# HACKERCARD.net
KiCad netlist of a schematic drawn in EasyEDA Pro
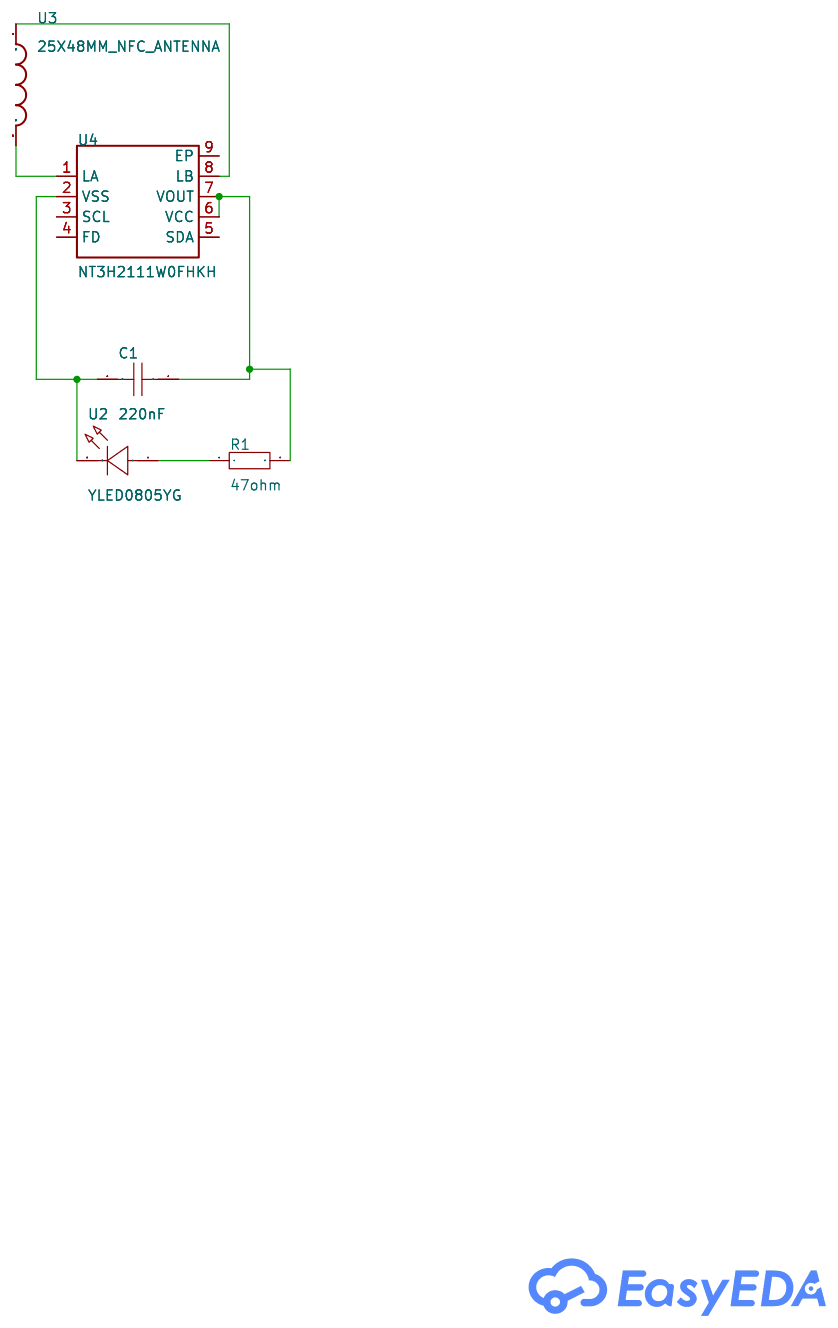
[diagram p0: schematic sheet]

(export (version "E")
  (design (tool "Eeschema 10.0.6"))
  (components
    (comp (ref "C1")
      (value "220nF")
      (footprint "easyedapro:C0603")
      (libsource (lib "easyedapro") (part "CAP"))
    )
    (comp (ref "R1")
      (value "47ohm")
      (footprint "easyedapro:R0603")
      (libsource (lib "easyedapro") (part "Res"))
    )
    (comp (ref "U2")
      (value "YLED0805YG")
      (footprint "easyedapro:LED0805-R-RD")
      (fields (field (name "Manufacturer") "YONGYUTAI(永裕泰)"))
      (libsource (lib "easyedapro") (part "YLED0805YG"))
    )
    (comp (ref "U3")
      (value "25X48MM_NFC_ANTENNA")
      (footprint "easyedapro:25X48MM_NFC_ANTENNA")
      (libsource (lib "easyedapro") (part "25X48MM_NFC_ANTENNA"))
    )
    (comp (ref "U4")
      (value "NT3H2111W0FHKH")
      (footprint "easyedapro:XQFN-8_L1.6-W1.6-P0.50-BL")
      (fields (field (name "Manufacturer") "NXP(恩智浦)"))
      (libsource (lib "easyedapro") (part "NT3H2111W0FHKH"))
    )
  )
  (nets
    (net (code "1") (name "Net-(R1-Pad1)") (class "Default")
      (node (ref "R1") (pin "1") (pinfunction "1_1") (pintype "input"))
      (node (ref "U2") (pin "1") (pinfunction "1_1") (pintype "unspecified"))
    )
    (net (code "2") (name "Net-(U4-LA)") (class "Default")
      (node (ref "U3") (pin "P$2") (pinfunction "P$2_P$2") (pintype "bidirectional"))
      (node (ref "U4") (pin "1") (pinfunction "LA_1") (pintype "unspecified"))
    )
    (net (code "3") (name "Net-(U4-LB)") (class "Default")
      (node (ref "U3") (pin "P$1") (pinfunction "P$1_P$1") (pintype "bidirectional"))
      (node (ref "U4") (pin "8") (pinfunction "LB_8") (pintype "unspecified"))
    )
    (net (code "4") (name "Net-(U4-VCC)") (class "Default")
      (node (ref "C1") (pin "1") (pinfunction "1_1") (pintype "input"))
      (node (ref "R1") (pin "2") (pinfunction "2_2") (pintype "input"))
      (node (ref "U4") (pin "6") (pinfunction "VCC_6") (pintype "unspecified"))
      (node (ref "U4") (pin "7") (pinfunction "VOUT_7") (pintype "unspecified"))
    )
    (net (code "5") (name "Net-(U4-VSS)") (class "Default")
      (node (ref "C1") (pin "2") (pinfunction "2_2") (pintype "input"))
      (node (ref "U2") (pin "2") (pinfunction "2_2") (pintype "unspecified"))
      (node (ref "U4") (pin "2") (pinfunction "VSS_2") (pintype "unspecified"))
    )
    (net (code "6") (name "unconnected-(U4-EP-Pad9)") (class "Default")
      (node (ref "U4") (pin "9") (pinfunction "EP_9") (pintype "unspecified"))
    )
    (net (code "7") (name "unconnected-(U4-FD-Pad4)") (class "Default")
      (node (ref "U4") (pin "4") (pinfunction "FD_4") (pintype "unspecified"))
    )
    (net (code "8") (name "unconnected-(U4-SCL-Pad3)") (class "Default")
      (node (ref "U4") (pin "3") (pinfunction "SCL_3") (pintype "unspecified"))
    )
    (net (code "9") (name "unconnected-(U4-SDA-Pad5)") (class "Default")
      (node (ref "U4") (pin "5") (pinfunction "SDA_5") (pintype "unspecified"))
    )
  )
)
